# SCH_DHT_projetos_2022-04-01.net
KiCad netlist of a schematic drawn in EasyEDA
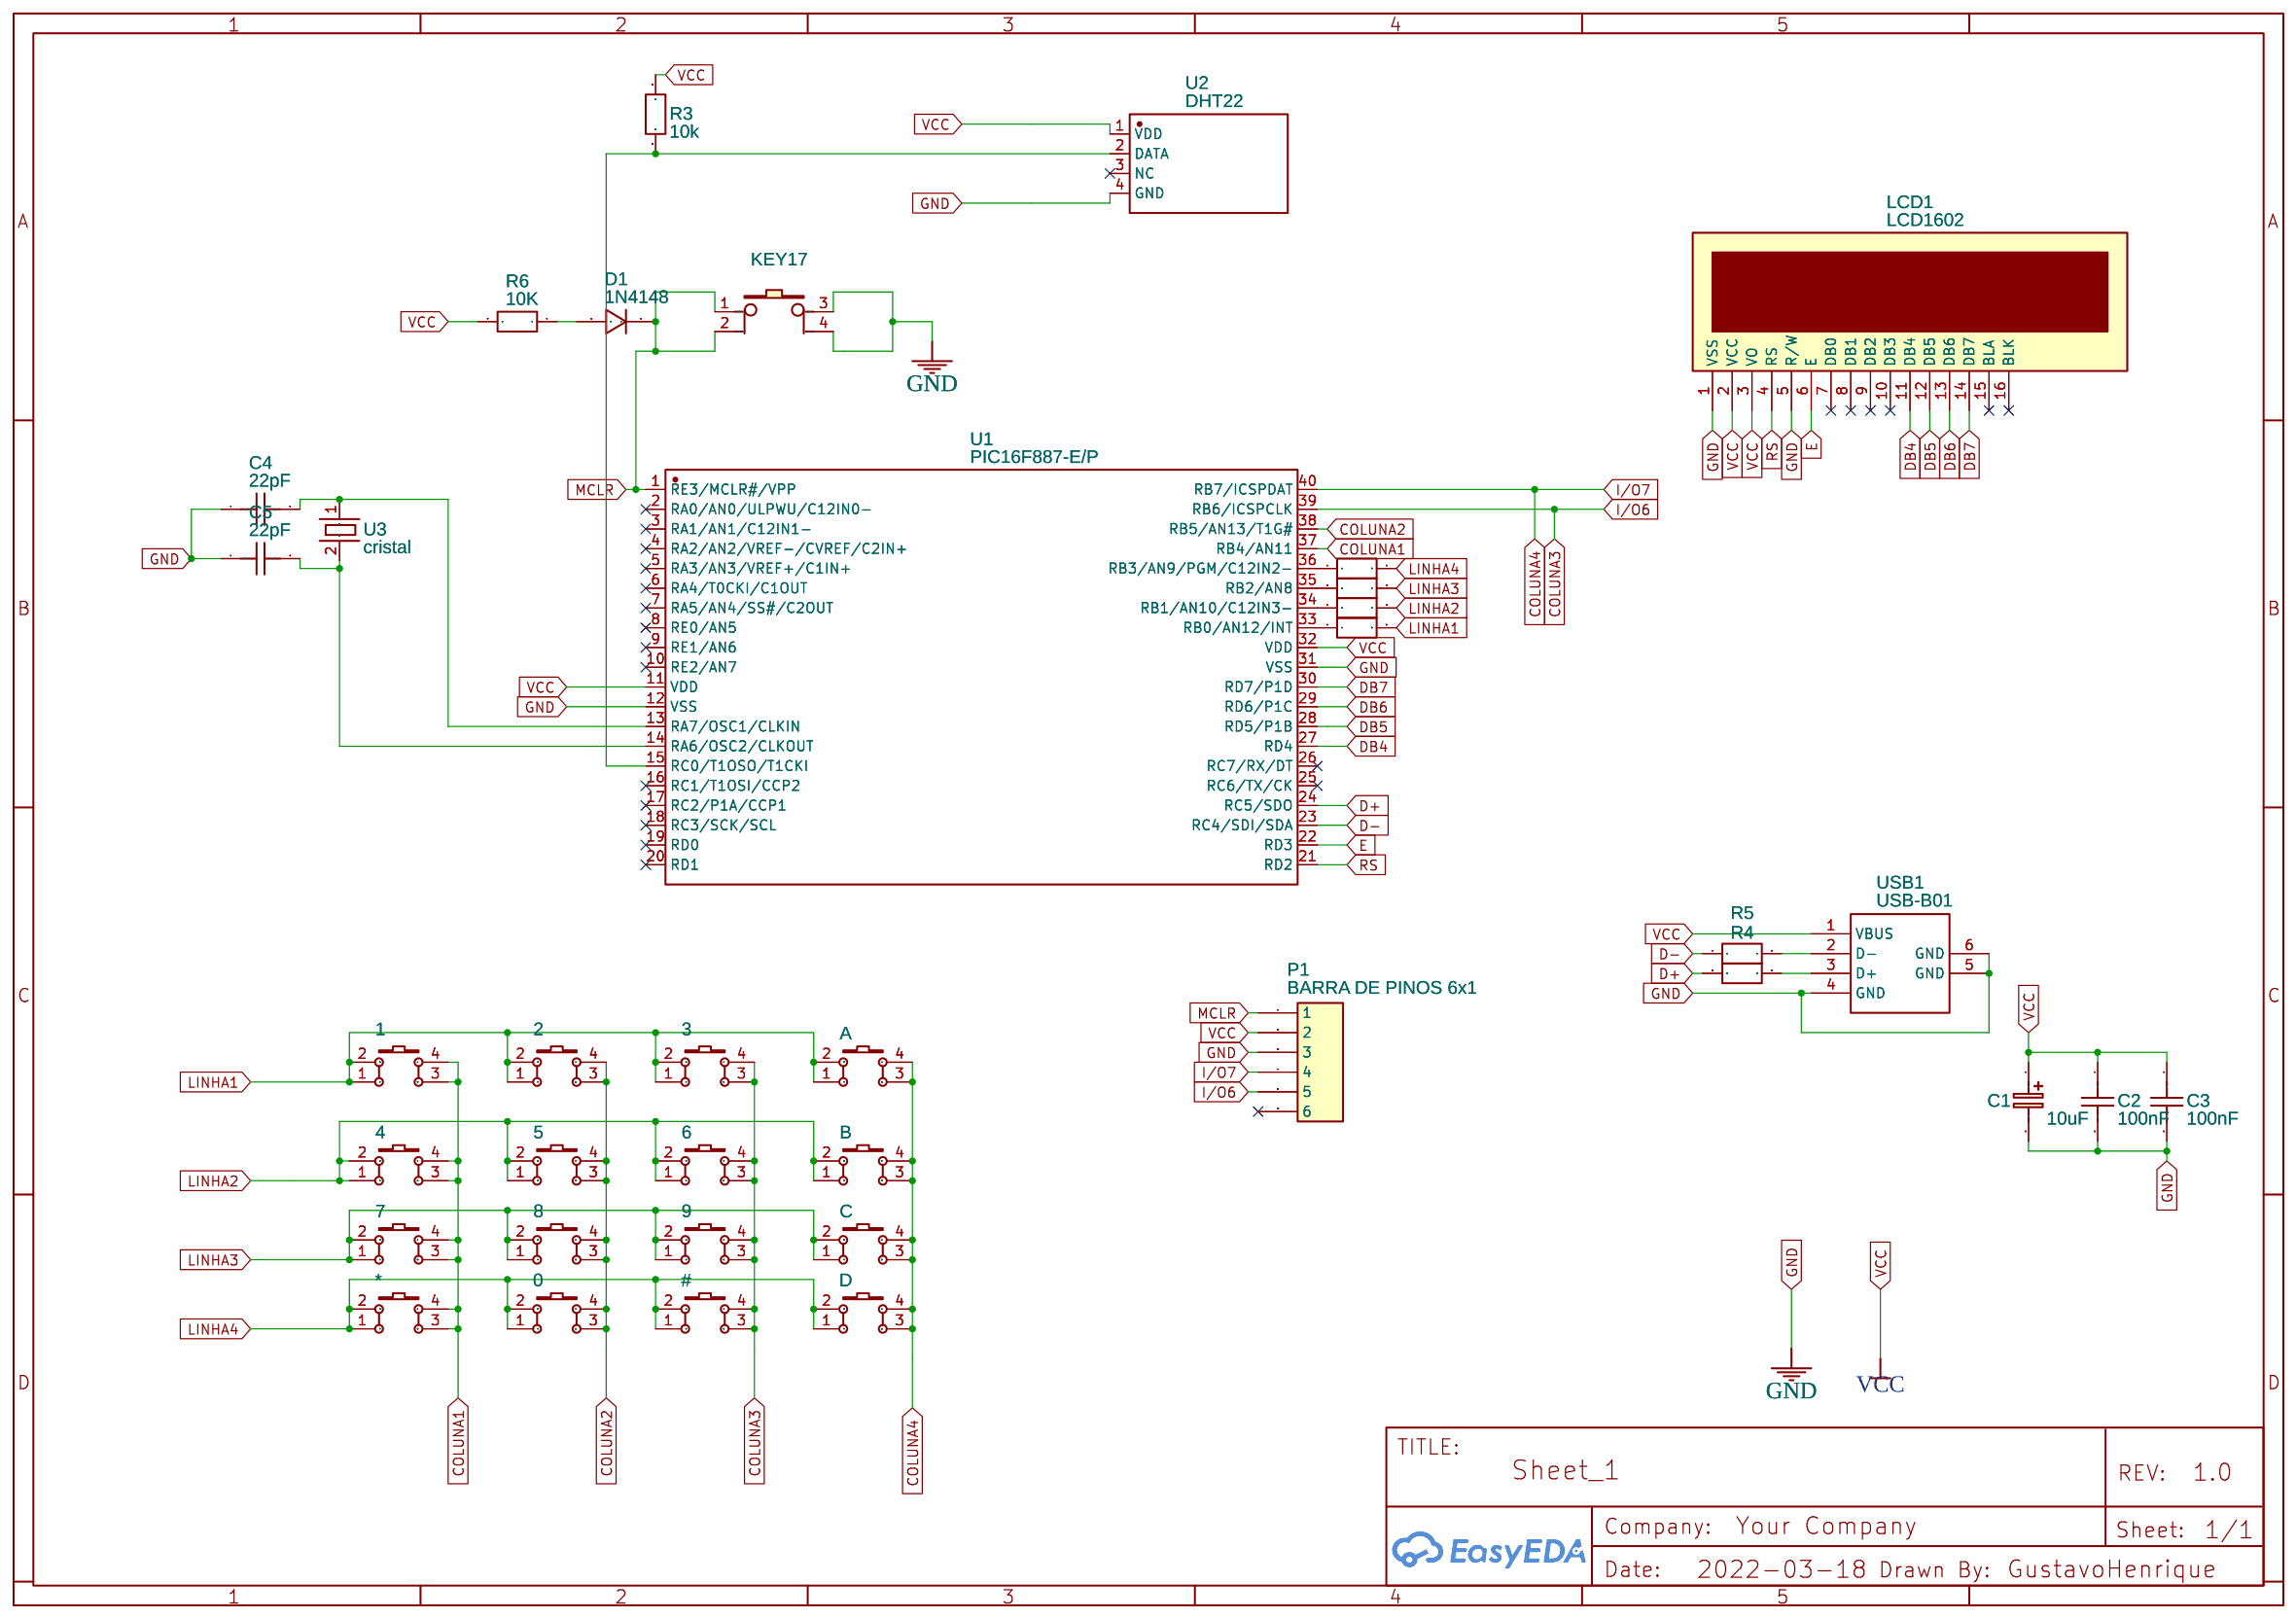
[diagram p0: schematic sheet]

(export (version "E")
  (design (tool "Eeschema 10.0.6"))
  (components
    (comp (ref "C1") (value "10uF") (libsource (lib "") (part "C_Tan_SMD_A_EU")))
    (comp (ref "C2") (value "100nF") (libsource (lib "") (part "C_0603_US")))
    (comp (ref "C3") (value "100nF") (libsource (lib "") (part "C_0603_US")))
    (comp (ref "C4")
      (value "22pF")
      (fields
        (field (name "BOM_Manufacturer Part") "CS1608X7R105K250NRB")
        (field (name "BOM_Supplier Part") "C513775")
      )
      (libsource (lib "") (part "CS1608X7R105K250NRB"))
    )
    (comp (ref "C5")
      (value "22pF")
      (fields
        (field (name "BOM_Manufacturer Part") "CS1608X7R105K250NRB")
        (field (name "BOM_Supplier Part") "C513775")
      )
      (libsource (lib "") (part "CS1608X7R105K250NRB"))
    )
    (comp (ref "D1")
      (value "1N4148")
      (fields (field (name "BOM_Manufacturer Part") "1N4007W") (field (name "BOM_Supplier Part") "C328592"))
      (libsource (lib "") (part "1N4007W"))
    )
    (comp (ref "KEY1")
      (value "1")
      (fields
        (field (name "BOM_Manufacturer Part") "K2-1102DP-E4SW-04")
        (field (name "BOM_Supplier Part") "C136684")
      )
      (libsource (lib "") (part "K4-6×6_TH"))
    )
    (comp (ref "KEY2")
      (value "4")
      (fields
        (field (name "BOM_Manufacturer Part") "K2-1102DP-E4SW-04")
        (field (name "BOM_Supplier Part") "C136684")
      )
      (libsource (lib "") (part "K4-6×6_TH"))
    )
    (comp (ref "KEY3")
      (value "7")
      (fields
        (field (name "BOM_Manufacturer Part") "K2-1102DP-E4SW-04")
        (field (name "BOM_Supplier Part") "C136684")
      )
      (libsource (lib "") (part "K4-6×6_TH"))
    )
    (comp (ref "KEY4")
      (value "*")
      (fields
        (field (name "BOM_Manufacturer Part") "K2-1102DP-E4SW-04")
        (field (name "BOM_Supplier Part") "C136684")
      )
      (libsource (lib "") (part "K4-6×6_TH"))
    )
    (comp (ref "KEY5")
      (value "0")
      (fields
        (field (name "BOM_Manufacturer Part") "K2-1102DP-E4SW-04")
        (field (name "BOM_Supplier Part") "C136684")
      )
      (libsource (lib "") (part "K4-6×6_TH"))
    )
    (comp (ref "KEY6")
      (value "8")
      (fields
        (field (name "BOM_Manufacturer Part") "K2-1102DP-E4SW-04")
        (field (name "BOM_Supplier Part") "C136684")
      )
      (libsource (lib "") (part "K4-6×6_TH"))
    )
    (comp (ref "KEY7")
      (value "5")
      (fields
        (field (name "BOM_Manufacturer Part") "K2-1102DP-E4SW-04")
        (field (name "BOM_Supplier Part") "C136684")
      )
      (libsource (lib "") (part "K4-6×6_TH"))
    )
    (comp (ref "KEY8")
      (value "2")
      (fields
        (field (name "BOM_Manufacturer Part") "K2-1102DP-E4SW-04")
        (field (name "BOM_Supplier Part") "C136684")
      )
      (libsource (lib "") (part "K4-6×6_TH"))
    )
    (comp (ref "KEY9")
      (value "#")
      (fields
        (field (name "BOM_Manufacturer Part") "K2-1102DP-E4SW-04")
        (field (name "BOM_Supplier Part") "C136684")
      )
      (libsource (lib "") (part "K4-6×6_TH"))
    )
    (comp (ref "KEY10")
      (value "9")
      (fields
        (field (name "BOM_Manufacturer Part") "K2-1102DP-E4SW-04")
        (field (name "BOM_Supplier Part") "C136684")
      )
      (libsource (lib "") (part "K4-6×6_TH"))
    )
    (comp (ref "KEY11")
      (value "6")
      (fields
        (field (name "BOM_Manufacturer Part") "K2-1102DP-E4SW-04")
        (field (name "BOM_Supplier Part") "C136684")
      )
      (libsource (lib "") (part "K4-6×6_TH"))
    )
    (comp (ref "KEY12")
      (value "3")
      (fields
        (field (name "BOM_Manufacturer Part") "K2-1102DP-E4SW-04")
        (field (name "BOM_Supplier Part") "C136684")
      )
      (libsource (lib "") (part "K4-6×6_TH"))
    )
    (comp (ref "KEY13")
      (value "D")
      (fields
        (field (name "BOM_Manufacturer Part") "K2-1102DP-E4SW-04")
        (field (name "BOM_Supplier Part") "C136684")
      )
      (libsource (lib "") (part "K4-6×6_TH"))
    )
    (comp (ref "KEY14")
      (value "C")
      (fields
        (field (name "BOM_Manufacturer Part") "K2-1102DP-E4SW-04")
        (field (name "BOM_Supplier Part") "C136684")
      )
      (libsource (lib "") (part "K4-6×6_TH"))
    )
    (comp (ref "KEY15")
      (value "B")
      (fields
        (field (name "BOM_Manufacturer Part") "K2-1102DP-E4SW-04")
        (field (name "BOM_Supplier Part") "C136684")
      )
      (libsource (lib "") (part "K4-6×6_TH"))
    )
    (comp (ref "KEY16")
      (value "A")
      (fields
        (field (name "BOM_Manufacturer Part") "K2-1102DP-E4SW-04")
        (field (name "BOM_Supplier Part") "C136684")
      )
      (libsource (lib "") (part "K4-6×6_TH"))
    )
    (comp (ref "KEY17")
      (value "button6*6*8.5")
      (fields (field (name "BOM_Supplier Part") "C59980"))
      (libsource (lib "") (part "button6*6*8.5"))
    )
    (comp (ref "LCD1")
      (value "LCD1602")
      (fields
        (field (name "BOM_Manufacturer Part") "LCM1602K-NSW-BBW")
        (field (name "BOM_Supplier Part") "C83275")
      )
      (libsource (lib "") (part "LCD1602"))
    )
    (comp (ref "P1") (value "BARRA DE PINOS 6x1") (libsource (lib "") (part "BARRA DE PINOS 6x1")))
    (comp (ref "R1") (value "1k") (libsource (lib "") (part "R_0603_EU")))
    (comp (ref "R2") (value "1k") (libsource (lib "") (part "R_0603_EU")))
    (comp (ref "R3") (value "10k") (libsource (lib "") (part "R_0603_EU_1")))
    (comp (ref "R4") (value "27") (libsource (lib "") (part "R_0603_EU")))
    (comp (ref "R5") (value "27") (libsource (lib "") (part "R_0603_EU")))
    (comp (ref "R6") (value "10K") (libsource (lib "") (part "R_0603_EU_2")))
    (comp (ref "R7") (value "1k") (libsource (lib "") (part "R_0603_EU")))
    (comp (ref "R8") (value "1k") (libsource (lib "") (part "R_0603_EU")))
    (comp (ref "U1")
      (value "PIC16F887-E/P")
      (fields (field (name "BOM_Supplier Part") "C647863"))
      (libsource (lib "") (part "PIC16F887-E/P"))
    )
    (comp (ref "U2")
      (value "DHT22")
      (fields (field (name "BOM_Manufacturer Part") "DHT11") (field (name "BOM_Supplier Part") "C117051"))
      (libsource (lib "") (part "DHT11"))
    )
    (comp (ref "U3") (value "cristal") (libsource (lib "") (part "cristal")))
    (comp (ref "USB1")
      (value "USB-B01")
      (fields (field (name "BOM_Supplier Part") "C498173"))
      (libsource (lib "") (part "USB-B01"))
    )
  )
  (nets
    (net (code "1") (name "COLUNA1") (class "Default")
      (node (ref "KEY1") (pin "3") (pinfunction "3_3") (pintype "unspecified"))
      (node (ref "KEY1") (pin "4") (pinfunction "4_4") (pintype "unspecified"))
      (node (ref "KEY2") (pin "3") (pinfunction "3_3") (pintype "unspecified"))
      (node (ref "KEY2") (pin "4") (pinfunction "4_4") (pintype "unspecified"))
      (node (ref "KEY3") (pin "3") (pinfunction "3_3") (pintype "unspecified"))
      (node (ref "KEY3") (pin "4") (pinfunction "4_4") (pintype "unspecified"))
      (node (ref "KEY4") (pin "3") (pinfunction "3_3") (pintype "unspecified"))
      (node (ref "KEY4") (pin "4") (pinfunction "4_4") (pintype "unspecified"))
      (node (ref "U1") (pin "37") (pinfunction "RB4/AN11_37") (pintype "unspecified"))
    )
    (net (code "2") (name "COLUNA2") (class "Default")
      (node (ref "KEY5") (pin "3") (pinfunction "3_3") (pintype "unspecified"))
      (node (ref "KEY5") (pin "4") (pinfunction "4_4") (pintype "unspecified"))
      (node (ref "KEY6") (pin "3") (pinfunction "3_3") (pintype "unspecified"))
      (node (ref "KEY6") (pin "4") (pinfunction "4_4") (pintype "unspecified"))
      (node (ref "KEY7") (pin "3") (pinfunction "3_3") (pintype "unspecified"))
      (node (ref "KEY7") (pin "4") (pinfunction "4_4") (pintype "unspecified"))
      (node (ref "KEY8") (pin "3") (pinfunction "3_3") (pintype "unspecified"))
      (node (ref "KEY8") (pin "4") (pinfunction "4_4") (pintype "unspecified"))
      (node (ref "U1") (pin "38") (pinfunction "RB5/AN13/T1G#_38") (pintype "unspecified"))
    )
    (net (code "3") (name "COLUNA3") (class "Default")
      (node (ref "KEY10") (pin "3") (pinfunction "3_3") (pintype "unspecified"))
      (node (ref "KEY10") (pin "4") (pinfunction "4_4") (pintype "unspecified"))
      (node (ref "KEY11") (pin "3") (pinfunction "3_3") (pintype "unspecified"))
      (node (ref "KEY11") (pin "4") (pinfunction "4_4") (pintype "unspecified"))
      (node (ref "KEY12") (pin "3") (pinfunction "3_3") (pintype "unspecified"))
      (node (ref "KEY12") (pin "4") (pinfunction "4_4") (pintype "unspecified"))
      (node (ref "KEY9") (pin "3") (pinfunction "3_3") (pintype "unspecified"))
      (node (ref "KEY9") (pin "4") (pinfunction "4_4") (pintype "unspecified"))
      (node (ref "P1") (pin "5") (pinfunction "5_5") (pintype "input"))
      (node (ref "U1") (pin "39") (pinfunction "RB6/ICSPCLK_39") (pintype "unspecified"))
    )
    (net (code "4") (name "COLUNA4") (class "Default")
      (node (ref "KEY13") (pin "3") (pinfunction "3_3") (pintype "unspecified"))
      (node (ref "KEY13") (pin "4") (pinfunction "4_4") (pintype "unspecified"))
      (node (ref "KEY14") (pin "3") (pinfunction "3_3") (pintype "unspecified"))
      (node (ref "KEY14") (pin "4") (pinfunction "4_4") (pintype "unspecified"))
      (node (ref "KEY15") (pin "3") (pinfunction "3_3") (pintype "unspecified"))
      (node (ref "KEY15") (pin "4") (pinfunction "4_4") (pintype "unspecified"))
      (node (ref "KEY16") (pin "3") (pinfunction "3_3") (pintype "unspecified"))
      (node (ref "KEY16") (pin "4") (pinfunction "4_4") (pintype "unspecified"))
      (node (ref "P1") (pin "4") (pinfunction "4_4") (pintype "input"))
      (node (ref "U1") (pin "40") (pinfunction "RB7/ICSPDAT_40") (pintype "unspecified"))
    )
    (net (code "5") (name "D+") (class "Default")
      (node (ref "R4") (pin "1") (pinfunction "1_1") (pintype "unspecified"))
      (node (ref "U1") (pin "24") (pinfunction "RC5/SDO_24") (pintype "unspecified"))
    )
    (net (code "6") (name "D-") (class "Default")
      (node (ref "R5") (pin "1") (pinfunction "1_1") (pintype "unspecified"))
      (node (ref "U1") (pin "23") (pinfunction "RC4/SDI/SDA_23") (pintype "unspecified"))
    )
    (net (code "7") (name "DB4") (class "Default")
      (node (ref "LCD1") (pin "11") (pinfunction "DB4_11") (pintype "unspecified"))
      (node (ref "U1") (pin "27") (pinfunction "RD4_27") (pintype "unspecified"))
    )
    (net (code "8") (name "DB5") (class "Default")
      (node (ref "LCD1") (pin "12") (pinfunction "DB5_12") (pintype "unspecified"))
      (node (ref "U1") (pin "28") (pinfunction "RD5/P1B_28") (pintype "unspecified"))
    )
    (net (code "9") (name "DB6") (class "Default")
      (node (ref "LCD1") (pin "13") (pinfunction "DB6_13") (pintype "unspecified"))
      (node (ref "U1") (pin "29") (pinfunction "RD6/P1C_29") (pintype "unspecified"))
    )
    (net (code "10") (name "DB7") (class "Default")
      (node (ref "LCD1") (pin "14") (pinfunction "DB7_14") (pintype "unspecified"))
      (node (ref "U1") (pin "30") (pinfunction "RD7/P1D_30") (pintype "unspecified"))
    )
    (net (code "11") (name "E") (class "Default")
      (node (ref "LCD1") (pin "6") (pinfunction "E_6") (pintype "unspecified"))
      (node (ref "U1") (pin "22") (pinfunction "RD3_22") (pintype "unspecified"))
    )
    (net (code "12") (name "GND") (class "Default")
      (node (ref "C1") (pin "2") (pinfunction "2_2") (pintype "unspecified"))
      (node (ref "C2") (pin "2") (pinfunction "2_2") (pintype "unspecified"))
      (node (ref "C3") (pin "2") (pinfunction "2_2") (pintype "unspecified"))
      (node (ref "C4") (pin "1") (pinfunction "1_1") (pintype "unspecified"))
      (node (ref "C5") (pin "1") (pinfunction "1_1") (pintype "unspecified"))
      (node (ref "KEY17") (pin "3") (pinfunction "3_3") (pintype "input"))
      (node (ref "KEY17") (pin "4") (pinfunction "4_4") (pintype "input"))
      (node (ref "LCD1") (pin "1") (pinfunction "VSS_1") (pintype "unspecified"))
      (node (ref "LCD1") (pin "5") (pinfunction "R/W_5") (pintype "unspecified"))
      (node (ref "P1") (pin "3") (pinfunction "3_3") (pintype "input"))
      (node (ref "U1") (pin "12") (pinfunction "VSS_12") (pintype "unspecified"))
      (node (ref "U1") (pin "31") (pinfunction "VSS_31") (pintype "unspecified"))
      (node (ref "U2") (pin "4") (pinfunction "GND_4") (pintype "unspecified"))
      (node (ref "USB1") (pin "4") (pinfunction "GND_4") (pintype "unspecified"))
      (node (ref "USB1") (pin "5") (pinfunction "GND_5") (pintype "unspecified"))
      (node (ref "USB1") (pin "6") (pinfunction "GND_6") (pintype "unspecified"))
    )
    (net (code "13") (name "LINHA1") (class "Default")
      (node (ref "KEY1") (pin "1") (pinfunction "1_1") (pintype "unspecified"))
      (node (ref "KEY1") (pin "2") (pinfunction "2_2") (pintype "unspecified"))
      (node (ref "KEY12") (pin "1") (pinfunction "1_1") (pintype "unspecified"))
      (node (ref "KEY12") (pin "2") (pinfunction "2_2") (pintype "unspecified"))
      (node (ref "KEY16") (pin "1") (pinfunction "1_1") (pintype "unspecified"))
      (node (ref "KEY16") (pin "2") (pinfunction "2_2") (pintype "unspecified"))
      (node (ref "KEY8") (pin "1") (pinfunction "1_1") (pintype "unspecified"))
      (node (ref "KEY8") (pin "2") (pinfunction "2_2") (pintype "unspecified"))
      (node (ref "R8") (pin "2") (pinfunction "2_2") (pintype "unspecified"))
    )
    (net (code "14") (name "LINHA2") (class "Default")
      (node (ref "KEY11") (pin "1") (pinfunction "1_1") (pintype "unspecified"))
      (node (ref "KEY11") (pin "2") (pinfunction "2_2") (pintype "unspecified"))
      (node (ref "KEY15") (pin "1") (pinfunction "1_1") (pintype "unspecified"))
      (node (ref "KEY15") (pin "2") (pinfunction "2_2") (pintype "unspecified"))
      (node (ref "KEY2") (pin "1") (pinfunction "1_1") (pintype "unspecified"))
      (node (ref "KEY2") (pin "2") (pinfunction "2_2") (pintype "unspecified"))
      (node (ref "KEY7") (pin "1") (pinfunction "1_1") (pintype "unspecified"))
      (node (ref "KEY7") (pin "2") (pinfunction "2_2") (pintype "unspecified"))
      (node (ref "R7") (pin "2") (pinfunction "2_2") (pintype "unspecified"))
    )
    (net (code "15") (name "LINHA3") (class "Default")
      (node (ref "KEY10") (pin "1") (pinfunction "1_1") (pintype "unspecified"))
      (node (ref "KEY10") (pin "2") (pinfunction "2_2") (pintype "unspecified"))
      (node (ref "KEY14") (pin "1") (pinfunction "1_1") (pintype "unspecified"))
      (node (ref "KEY14") (pin "2") (pinfunction "2_2") (pintype "unspecified"))
      (node (ref "KEY3") (pin "1") (pinfunction "1_1") (pintype "unspecified"))
      (node (ref "KEY3") (pin "2") (pinfunction "2_2") (pintype "unspecified"))
      (node (ref "KEY6") (pin "1") (pinfunction "1_1") (pintype "unspecified"))
      (node (ref "KEY6") (pin "2") (pinfunction "2_2") (pintype "unspecified"))
      (node (ref "R2") (pin "2") (pinfunction "2_2") (pintype "unspecified"))
    )
    (net (code "16") (name "LINHA4") (class "Default")
      (node (ref "KEY13") (pin "1") (pinfunction "1_1") (pintype "unspecified"))
      (node (ref "KEY13") (pin "2") (pinfunction "2_2") (pintype "unspecified"))
      (node (ref "KEY4") (pin "1") (pinfunction "1_1") (pintype "unspecified"))
      (node (ref "KEY4") (pin "2") (pinfunction "2_2") (pintype "unspecified"))
      (node (ref "KEY5") (pin "1") (pinfunction "1_1") (pintype "unspecified"))
      (node (ref "KEY5") (pin "2") (pinfunction "2_2") (pintype "unspecified"))
      (node (ref "KEY9") (pin "1") (pinfunction "1_1") (pintype "unspecified"))
      (node (ref "KEY9") (pin "2") (pinfunction "2_2") (pintype "unspecified"))
      (node (ref "R1") (pin "2") (pinfunction "2_2") (pintype "unspecified"))
    )
    (net (code "17") (name "MCLR") (class "Default")
      (node (ref "D1") (pin "1") (pinfunction "1_1") (pintype "unspecified"))
      (node (ref "KEY17") (pin "1") (pinfunction "1_1") (pintype "input"))
      (node (ref "KEY17") (pin "2") (pinfunction "2_2") (pintype "input"))
      (node (ref "P1") (pin "1") (pinfunction "1_1") (pintype "input"))
      (node (ref "U1") (pin "1") (pinfunction "RE3/MCLR#/VPP_1") (pintype "unspecified"))
    )
    (net (code "18") (name "Net-(D1-Pad2)") (class "Default")
      (node (ref "D1") (pin "2") (pinfunction "2_2") (pintype "unspecified"))
      (node (ref "R6") (pin "1") (pinfunction "1_1") (pintype "unspecified"))
    )
    (net (code "19") (name "Net-(U1-RA6{slash}OSC2{slash}CLKOUT)") (class "Default")
      (node (ref "C5") (pin "2") (pinfunction "2_2") (pintype "unspecified"))
      (node (ref "U1") (pin "14") (pinfunction "RA6/OSC2/CLKOUT_14") (pintype "unspecified"))
      (node (ref "U3") (pin "2") (pinfunction "2_2") (pintype "unspecified"))
    )
    (net (code "20") (name "Net-(U1-RA7{slash}OSC1{slash}CLKIN)") (class "Default")
      (node (ref "C4") (pin "2") (pinfunction "2_2") (pintype "unspecified"))
      (node (ref "U1") (pin "13") (pinfunction "RA7/OSC1/CLKIN_13") (pintype "unspecified"))
      (node (ref "U3") (pin "1") (pinfunction "1_1") (pintype "unspecified"))
    )
    (net (code "21") (name "Net-(U1-RB0{slash}AN12{slash}INT)") (class "Default")
      (node (ref "R8") (pin "1") (pinfunction "1_1") (pintype "unspecified"))
      (node (ref "U1") (pin "33") (pinfunction "RB0/AN12/INT_33") (pintype "unspecified"))
    )
    (net (code "22") (name "Net-(U1-RB1{slash}AN10{slash}C12IN3-)") (class "Default")
      (node (ref "R7") (pin "1") (pinfunction "1_1") (pintype "unspecified"))
      (node (ref "U1") (pin "34") (pinfunction "RB1/AN10/C12IN3-_34") (pintype "unspecified"))
    )
    (net (code "23") (name "Net-(U1-RB2{slash}AN8)") (class "Default")
      (node (ref "R2") (pin "1") (pinfunction "1_1") (pintype "unspecified"))
      (node (ref "U1") (pin "35") (pinfunction "RB2/AN8_35") (pintype "unspecified"))
    )
    (net (code "24") (name "Net-(U1-RB3{slash}AN9{slash}PGM{slash}C12IN2-)") (class "Default")
      (node (ref "R1") (pin "1") (pinfunction "1_1") (pintype "unspecified"))
      (node (ref "U1") (pin "36") (pinfunction "RB3/AN9/PGM/C12IN2-_36") (pintype "unspecified"))
    )
    (net (code "25") (name "Net-(U1-RC0{slash}T1OSO{slash}T1CKI)") (class "Default")
      (node (ref "R3") (pin "2") (pinfunction "2_2") (pintype "unspecified"))
      (node (ref "U1") (pin "15") (pinfunction "RC0/T1OSO/T1CKI_15") (pintype "unspecified"))
      (node (ref "U2") (pin "2") (pinfunction "DATA_2") (pintype "unspecified"))
    )
    (net (code "26") (name "Net-(USB1-D+)") (class "Default")
      (node (ref "R4") (pin "2") (pinfunction "2_2") (pintype "unspecified"))
      (node (ref "USB1") (pin "3") (pinfunction "D+_3") (pintype "unspecified"))
    )
    (net (code "27") (name "Net-(USB1-D-)") (class "Default")
      (node (ref "R5") (pin "2") (pinfunction "2_2") (pintype "unspecified"))
      (node (ref "USB1") (pin "2") (pinfunction "D-_2") (pintype "unspecified"))
    )
    (net (code "28") (name "RS") (class "Default")
      (node (ref "LCD1") (pin "4") (pinfunction "RS_4") (pintype "unspecified"))
      (node (ref "U1") (pin "21") (pinfunction "RD2_21") (pintype "unspecified"))
    )
    (net (code "29") (name "VCC") (class "Default")
      (node (ref "C1") (pin "1") (pinfunction "1_1") (pintype "unspecified"))
      (node (ref "C2") (pin "1") (pinfunction "1_1") (pintype "unspecified"))
      (node (ref "C3") (pin "1") (pinfunction "1_1") (pintype "unspecified"))
      (node (ref "LCD1") (pin "2") (pinfunction "VCC_2") (pintype "unspecified"))
      (node (ref "LCD1") (pin "3") (pinfunction "VO_3") (pintype "unspecified"))
      (node (ref "P1") (pin "2") (pinfunction "2_2") (pintype "input"))
      (node (ref "R3") (pin "1") (pinfunction "1_1") (pintype "unspecified"))
      (node (ref "R6") (pin "2") (pinfunction "2_2") (pintype "unspecified"))
      (node (ref "U1") (pin "11") (pinfunction "VDD_11") (pintype "unspecified"))
      (node (ref "U1") (pin "32") (pinfunction "VDD_32") (pintype "unspecified"))
      (node (ref "U2") (pin "1") (pinfunction "VDD_1") (pintype "unspecified"))
      (node (ref "USB1") (pin "1") (pinfunction "VBUS_1") (pintype "unspecified"))
    )
    (net (code "30") (name "unconnected-(LCD1-BLA-Pad15)") (class "Default")
      (node (ref "LCD1") (pin "15") (pinfunction "BLA_15") (pintype "unspecified+no_connect"))
    )
    (net (code "31") (name "unconnected-(LCD1-BLK-Pad16)") (class "Default")
      (node (ref "LCD1") (pin "16") (pinfunction "BLK_16") (pintype "unspecified+no_connect"))
    )
    (net (code "32") (name "unconnected-(LCD1-DB0-Pad7)") (class "Default")
      (node (ref "LCD1") (pin "7") (pinfunction "DB0_7") (pintype "unspecified+no_connect"))
    )
    (net (code "33") (name "unconnected-(LCD1-DB1-Pad8)") (class "Default")
      (node (ref "LCD1") (pin "8") (pinfunction "DB1_8") (pintype "unspecified+no_connect"))
    )
    (net (code "34") (name "unconnected-(LCD1-DB2-Pad9)") (class "Default")
      (node (ref "LCD1") (pin "9") (pinfunction "DB2_9") (pintype "unspecified+no_connect"))
    )
    (net (code "35") (name "unconnected-(LCD1-DB3-Pad10)") (class "Default")
      (node (ref "LCD1") (pin "10") (pinfunction "DB3_10") (pintype "unspecified+no_connect"))
    )
    (net (code "36") (name "unconnected-(P1-Pad6)") (class "Default")
      (node (ref "P1") (pin "6") (pinfunction "6_6") (pintype "input+no_connect"))
    )
    (net (code "37") (name "unconnected-(U1-RA0{slash}AN0{slash}ULPWU{slash}C12IN0--Pad2)") (class "Default")
      (node (ref "U1") (pin "2") (pinfunction "RA0/AN0/ULPWU/C12IN0-_2") (pintype "unspecified+no_connect"))
    )
    (net (code "38") (name "unconnected-(U1-RA1{slash}AN1{slash}C12IN1--Pad3)") (class "Default")
      (node (ref "U1") (pin "3") (pinfunction "RA1/AN1/C12IN1-_3") (pintype "unspecified+no_connect"))
    )
    (net (code "39") (name "unconnected-(U1-RA2{slash}AN2{slash}VREF-{slash}CVREF{slash}C2IN+-Pad4)") (class "Default")
      (node (ref "U1") (pin "4") (pinfunction "RA2/AN2/VREF-/CVREF/C2IN+_4") (pintype "unspecified+no_connect"))
    )
    (net (code "40") (name "unconnected-(U1-RA3{slash}AN3{slash}VREF+{slash}C1IN+-Pad5)") (class "Default")
      (node (ref "U1") (pin "5") (pinfunction "RA3/AN3/VREF+/C1IN+_5") (pintype "unspecified+no_connect"))
    )
    (net (code "41") (name "unconnected-(U1-RA4{slash}T0CKI{slash}C1OUT-Pad6)") (class "Default")
      (node (ref "U1") (pin "6") (pinfunction "RA4/T0CKI/C1OUT_6") (pintype "unspecified+no_connect"))
    )
    (net (code "42") (name "unconnected-(U1-RA5{slash}AN4{slash}SS#{slash}C2OUT-Pad7)") (class "Default")
      (node (ref "U1") (pin "7") (pinfunction "RA5/AN4/SS#/C2OUT_7") (pintype "unspecified+no_connect"))
    )
    (net (code "43") (name "unconnected-(U1-RC1{slash}T1OSI{slash}CCP2-Pad16)") (class "Default")
      (node (ref "U1") (pin "16") (pinfunction "RC1/T1OSI/CCP2_16") (pintype "unspecified+no_connect"))
    )
    (net (code "44") (name "unconnected-(U1-RC2{slash}P1A{slash}CCP1-Pad17)") (class "Default")
      (node (ref "U1") (pin "17") (pinfunction "RC2/P1A/CCP1_17") (pintype "unspecified+no_connect"))
    )
    (net (code "45") (name "unconnected-(U1-RC3{slash}SCK{slash}SCL-Pad18)") (class "Default")
      (node (ref "U1") (pin "18") (pinfunction "RC3/SCK/SCL_18") (pintype "unspecified+no_connect"))
    )
    (net (code "46") (name "unconnected-(U1-RC6{slash}TX{slash}CK-Pad25)") (class "Default")
      (node (ref "U1") (pin "25") (pinfunction "RC6/TX/CK_25") (pintype "unspecified+no_connect"))
    )
    (net (code "47") (name "unconnected-(U1-RC7{slash}RX{slash}DT-Pad26)") (class "Default")
      (node (ref "U1") (pin "26") (pinfunction "RC7/RX/DT_26") (pintype "unspecified+no_connect"))
    )
    (net (code "48") (name "unconnected-(U1-RD0-Pad19)") (class "Default")
      (node (ref "U1") (pin "19") (pinfunction "RD0_19") (pintype "unspecified+no_connect"))
    )
    (net (code "49") (name "unconnected-(U1-RD1-Pad20)") (class "Default")
      (node (ref "U1") (pin "20") (pinfunction "RD1_20") (pintype "unspecified+no_connect"))
    )
    (net (code "50") (name "unconnected-(U1-RE0{slash}AN5-Pad8)") (class "Default")
      (node (ref "U1") (pin "8") (pinfunction "RE0/AN5_8") (pintype "unspecified+no_connect"))
    )
    (net (code "51") (name "unconnected-(U1-RE1{slash}AN6-Pad9)") (class "Default")
      (node (ref "U1") (pin "9") (pinfunction "RE1/AN6_9") (pintype "unspecified+no_connect"))
    )
    (net (code "52") (name "unconnected-(U1-RE2{slash}AN7-Pad10)") (class "Default")
      (node (ref "U1") (pin "10") (pinfunction "RE2/AN7_10") (pintype "unspecified+no_connect"))
    )
    (net (code "53") (name "unconnected-(U2-NC-Pad3)") (class "Default")
      (node (ref "U2") (pin "3") (pinfunction "NC_3") (pintype "unspecified+no_connect"))
    )
  )
)
